# PowerSupply12v30A.net
KiCad netlist of a schematic drawn in Altium Designer
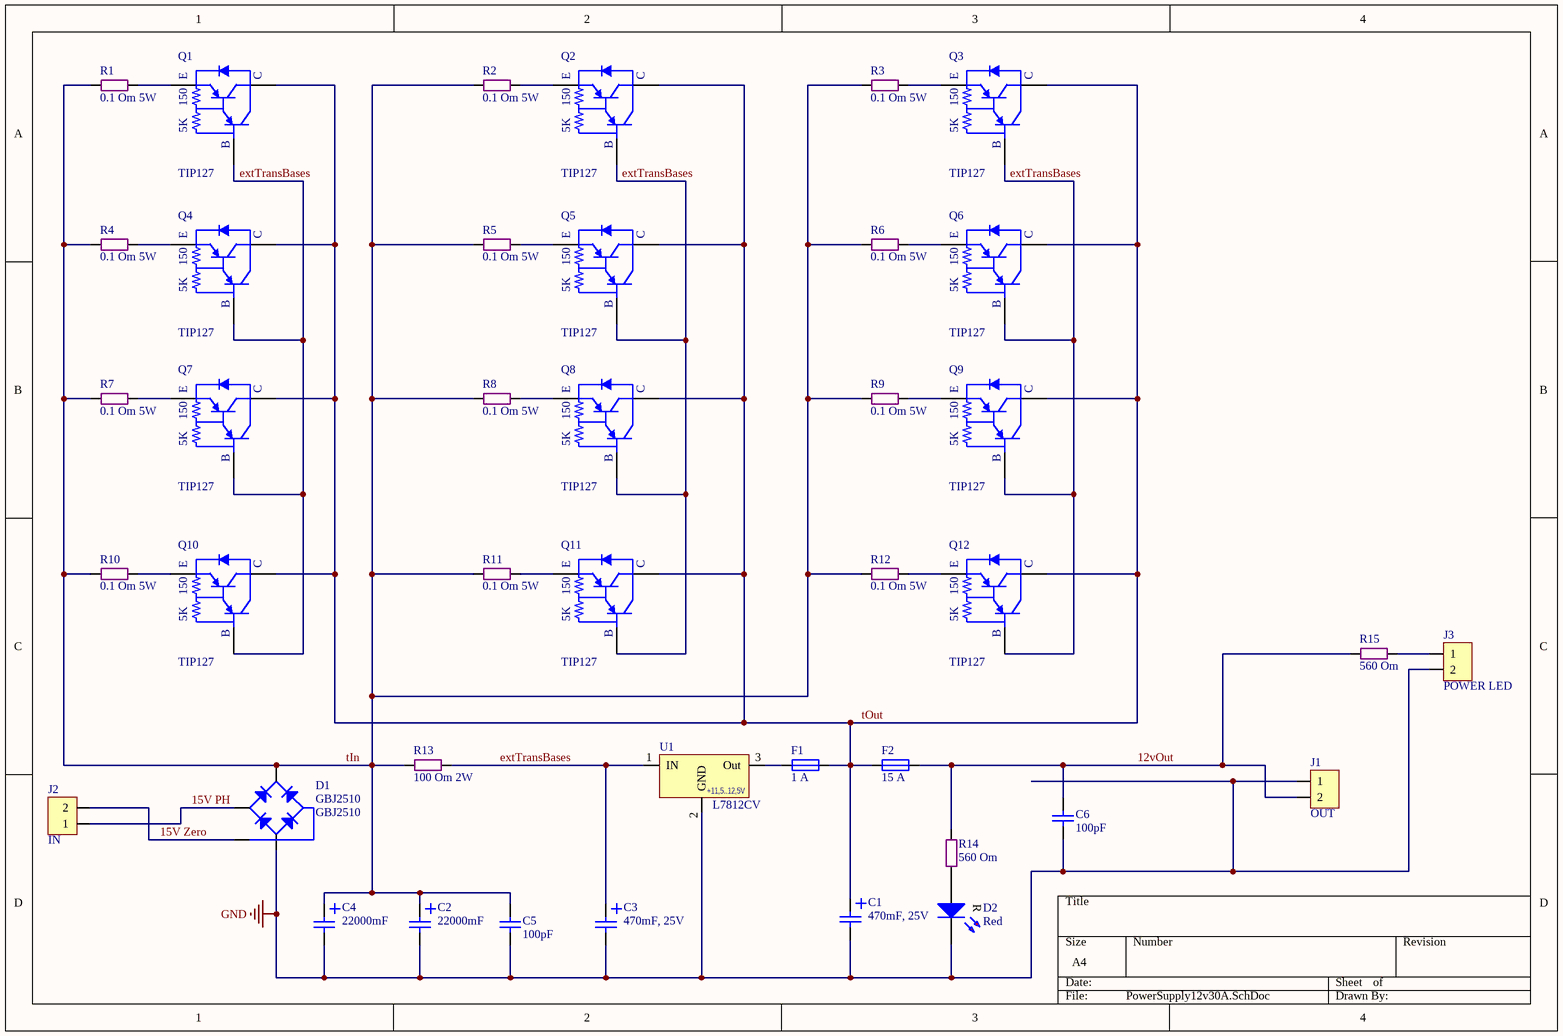
[diagram p0: PowerSupply12v30A.SchDoc]

(export (version "E")
  (design (tool "Eeschema 10.0.6"))
  (components
    (comp (ref "C1")
      (value "470mF, 25V")
      (footprint "Capacitor:Cap E p3.5mm D8xH12")
      (description "Capacitor")
      (libsource (lib "Capacitor") (part "Cap E 470mF x 25V"))
    )
    (comp (ref "C2")
      (value "22000mF")
      (footprint "Capacitor:Cap E p10mm D30mm (4p)")
      (description "Capacitor")
      (libsource (lib "Capacitor") (part "Cap E 22000mF x 25V"))
    )
    (comp (ref "C3")
      (value "470mF, 25V")
      (footprint "Capacitor:Cap E p3.5mm D8xH12")
      (description "Capacitor")
      (libsource (lib "Capacitor") (part "Cap E 470mF x 25V"))
    )
    (comp (ref "C4")
      (value "22000mF")
      (footprint "Capacitor:Cap E p10mm D30mm (4p)")
      (description "Capacitor")
      (libsource (lib "Capacitor") (part "Cap E 22000mF x 25V"))
    )
    (comp (ref "C5")
      (value "100pF")
      (footprint "Capacitor:SMD 1206 (3216)")
      (description "Capacitor")
      (libsource (lib "Capacitor") (part "Cap SMD 0402-1812"))
    )
    (comp (ref "C6")
      (value "100pF")
      (footprint "Capacitor:SMD 0805 (2012)")
      (description "Capacitor")
      (libsource (lib "Capacitor") (part "Cap SMD 0402-1812"))
    )
    (comp (ref "D1")
      (value "GBJ2510")
      (footprint "Diodes:GBJ")
      (description "25 A Diode Bridge")
      (fields (field (name "VOLTAGE") "1000V") (field (name "ALTIUM_VALUE") "GBJ2510"))
      (libsource (lib "Diodes") (part "Bridge GBJ2510"))
    )
    (comp (ref "D2")
      (value "Red")
      (footprint "LED:LED Round 5mm red")
      (description "1.8-2v 20mA, 4-5cd")
      (libsource (lib "LED") (part "Led Round 5mm Red"))
    )
    (comp (ref "F1")
      (value "1 A")
      (footprint "PassiveComponents:Fuse 9p")
      (description "Round fuse")
      (libsource (lib "PassiveComponents") (part "Fuse"))
    )
    (comp (ref "F2")
      (value "15 A")
      (footprint "PassiveComponents:Fuse 9p")
      (description "Round fuse")
      (libsource (lib "PassiveComponents") (part "Fuse"))
    )
    (comp (ref "J1")
      (value "OUT")
      (footprint "Connector:DG301 5mm 2p")
      (description "DG301 series")
      (libsource (lib "Connector") (part "DG301-5.0-2P12"))
    )
    (comp (ref "J2")
      (value "IN")
      (footprint "Connector:DG301 5mm 2p")
      (description "DG301 series")
      (libsource (lib "") (part "DG301-5.0-2P12_1"))
    )
    (comp (ref "J3")
      (value "POWER LED")
      (footprint "Connector:CWF-2 R")
      (description "CWF series")
      (libsource (lib "Connector") (part "CWF-2 (R)"))
    )
    (comp (ref "Q1")
      (value "TIP127")
      (footprint "GeneralCases:TO220-2")
      (description "PNP Darlington Bipolar Transistor")
      (libsource (lib "Transistor") (part "TIP127"))
    )
    (comp (ref "Q2")
      (value "TIP127")
      (footprint "GeneralCases:TO220-2")
      (description "PNP Darlington Bipolar Transistor")
      (libsource (lib "Transistor") (part "TIP127"))
    )
    (comp (ref "Q3")
      (value "TIP127")
      (footprint "GeneralCases:TO220-2")
      (description "PNP Darlington Bipolar Transistor")
      (libsource (lib "Transistor") (part "TIP127"))
    )
    (comp (ref "Q4")
      (value "TIP127")
      (footprint "GeneralCases:TO220-2")
      (description "PNP Darlington Bipolar Transistor")
      (libsource (lib "Transistor") (part "TIP127"))
    )
    (comp (ref "Q5")
      (value "TIP127")
      (footprint "GeneralCases:TO220-2")
      (description "PNP Darlington Bipolar Transistor")
      (libsource (lib "Transistor") (part "TIP127"))
    )
    (comp (ref "Q6")
      (value "TIP127")
      (footprint "GeneralCases:TO220-2")
      (description "PNP Darlington Bipolar Transistor")
      (libsource (lib "Transistor") (part "TIP127"))
    )
    (comp (ref "Q7")
      (value "TIP127")
      (footprint "GeneralCases:TO220-2")
      (description "PNP Darlington Bipolar Transistor")
      (libsource (lib "Transistor") (part "TIP127"))
    )
    (comp (ref "Q8")
      (value "TIP127")
      (footprint "GeneralCases:TO220-2")
      (description "PNP Darlington Bipolar Transistor")
      (libsource (lib "Transistor") (part "TIP127"))
    )
    (comp (ref "Q9")
      (value "TIP127")
      (footprint "GeneralCases:TO220-2")
      (description "PNP Darlington Bipolar Transistor")
      (libsource (lib "Transistor") (part "TIP127"))
    )
    (comp (ref "Q10")
      (value "TIP127")
      (footprint "GeneralCases:TO220-2")
      (description "PNP Darlington Bipolar Transistor")
      (libsource (lib "Transistor") (part "TIP127"))
    )
    (comp (ref "Q11")
      (value "TIP127")
      (footprint "GeneralCases:TO220-2")
      (description "PNP Darlington Bipolar Transistor")
      (libsource (lib "Transistor") (part "TIP127"))
    )
    (comp (ref "Q12")
      (value "TIP127")
      (footprint "GeneralCases:TO220-2")
      (description "PNP Darlington Bipolar Transistor")
      (libsource (lib "Transistor") (part "TIP127"))
    )
    (comp (ref "R1")
      (value "0.1 Om 5W")
      (footprint "PassiveComponents:Res 5W L22mm, p30mm")
      (description "5W Cement")
      (libsource (lib "PassiveComponents") (part "Res 5W"))
    )
    (comp (ref "R2")
      (value "0.1 Om 5W")
      (footprint "PassiveComponents:Res 5W L22mm, p30mm")
      (description "5W Cement")
      (libsource (lib "PassiveComponents") (part "Res 5W"))
    )
    (comp (ref "R3")
      (value "0.1 Om 5W")
      (footprint "PassiveComponents:Res 5W L22mm, p30mm")
      (description "5W Cement")
      (libsource (lib "PassiveComponents") (part "Res 5W"))
    )
    (comp (ref "R4")
      (value "0.1 Om 5W")
      (footprint "PassiveComponents:Res 5W L22mm, p30mm")
      (description "5W Cement")
      (libsource (lib "PassiveComponents") (part "Res 5W"))
    )
    (comp (ref "R5")
      (value "0.1 Om 5W")
      (footprint "PassiveComponents:Res 5W L22mm, p30mm")
      (description "5W Cement")
      (libsource (lib "PassiveComponents") (part "Res 5W"))
    )
    (comp (ref "R6")
      (value "0.1 Om 5W")
      (footprint "PassiveComponents:Res 5W L22mm, p30mm")
      (description "5W Cement")
      (libsource (lib "PassiveComponents") (part "Res 5W"))
    )
    (comp (ref "R7")
      (value "0.1 Om 5W")
      (footprint "PassiveComponents:Res 5W L22mm, p30mm")
      (description "5W Cement")
      (libsource (lib "PassiveComponents") (part "Res 5W"))
    )
    (comp (ref "R8")
      (value "0.1 Om 5W")
      (footprint "PassiveComponents:Res 5W L22mm, p30mm")
      (description "5W Cement")
      (libsource (lib "PassiveComponents") (part "Res 5W"))
    )
    (comp (ref "R9")
      (value "0.1 Om 5W")
      (footprint "PassiveComponents:Res 5W L22mm, p30mm")
      (description "5W Cement")
      (libsource (lib "PassiveComponents") (part "Res 5W"))
    )
    (comp (ref "R10")
      (value "0.1 Om 5W")
      (footprint "PassiveComponents:Res 5W L22mm, p30mm")
      (description "5W Cement")
      (libsource (lib "PassiveComponents") (part "Res 5W"))
    )
    (comp (ref "R11")
      (value "0.1 Om 5W")
      (footprint "PassiveComponents:Res 5W L22mm, p30mm")
      (description "5W Cement")
      (libsource (lib "PassiveComponents") (part "Res 5W"))
    )
    (comp (ref "R12")
      (value "0.1 Om 5W")
      (footprint "PassiveComponents:Res 5W L22mm, p30mm")
      (description "5W Cement")
      (libsource (lib "PassiveComponents") (part "Res 5W"))
    )
    (comp (ref "R13")
      (value "100 Om 2W")
      (footprint "PassiveComponents:Res p20.32 (9p) 2w")
      (description "5W Cement")
      (libsource (lib "PassiveComponents") (part "Res 2W"))
    )
    (comp (ref "R14")
      (value "560 Om")
      (footprint "PassiveComponents:Res p7.62 (4p) 0.25w")
      (libsource (lib "PassiveComponents") (part "Res Carbon"))
    )
    (comp (ref "R15")
      (value "560 Om")
      (footprint "PassiveComponents:Res p7.62 (4p) 0.25w")
      (libsource (lib "PassiveComponents") (part "Res Carbon"))
    )
    (comp (ref "U1")
      (value "L7812CV")
      (footprint "GeneralCases:TO220-2")
      (description "Voltage Regulator")
      (fields (field (name "MANUFACTURER") "ST") (field (name "V OUT") "+11,5..12,5V"))
      (libsource (lib "PowerAdjusment") (part "L7812CV"))
    )
  )
  (nets
    (net (code "1") (name "/12vOut") (class "Default")
      (node (ref "C6") (pin "1") (pinfunction "1_1") (pintype "passive"))
      (node (ref "F2") (pin "2") (pinfunction "2_2") (pintype "passive"))
      (node (ref "J1") (pin "2") (pinfunction "2_2") (pintype "passive"))
      (node (ref "R14") (pin "2") (pinfunction "2_2") (pintype "passive"))
      (node (ref "R15") (pin "2") (pinfunction "2_2") (pintype "passive"))
    )
    (net (code "2") (name "/15V PH") (class "Default")
      (node (ref "D1") (pin "P") (pinfunction "Ph_P") (pintype "passive"))
      (node (ref "J2") (pin "1") (pinfunction "1_1") (pintype "passive"))
    )
    (net (code "3") (name "/15V Zero") (class "Default")
      (node (ref "D1") (pin "Z") (pinfunction "Z_Z") (pintype "passive"))
      (node (ref "J2") (pin "2") (pinfunction "2_2") (pintype "passive"))
    )
    (net (code "4") (name "/extTransBases") (class "Default")
      (node (ref "C3") (pin "1") (pinfunction "1_1") (pintype "passive"))
      (node (ref "Q1") (pin "1") (pinfunction "B_1") (pintype "passive"))
      (node (ref "Q10") (pin "1") (pinfunction "B_1") (pintype "passive"))
      (node (ref "Q11") (pin "1") (pinfunction "B_1") (pintype "passive"))
      (node (ref "Q12") (pin "1") (pinfunction "B_1") (pintype "passive"))
      (node (ref "Q2") (pin "1") (pinfunction "B_1") (pintype "passive"))
      (node (ref "Q3") (pin "1") (pinfunction "B_1") (pintype "passive"))
      (node (ref "Q4") (pin "1") (pinfunction "B_1") (pintype "passive"))
      (node (ref "Q5") (pin "1") (pinfunction "B_1") (pintype "passive"))
      (node (ref "Q6") (pin "1") (pinfunction "B_1") (pintype "passive"))
      (node (ref "Q7") (pin "1") (pinfunction "B_1") (pintype "passive"))
      (node (ref "Q8") (pin "1") (pinfunction "B_1") (pintype "passive"))
      (node (ref "Q9") (pin "1") (pinfunction "B_1") (pintype "passive"))
      (node (ref "R13") (pin "2") (pinfunction "2_2") (pintype "passive"))
      (node (ref "U1") (pin "1") (pinfunction "IN_1") (pintype "power_in"))
    )
    (net (code "5") (name "/tIn") (class "Default")
      (node (ref "C2") (pin "1") (pinfunction "1_1") (pintype "passive"))
      (node (ref "C4") (pin "1") (pinfunction "1_1") (pintype "passive"))
      (node (ref "C5") (pin "1") (pinfunction "1_1") (pintype "passive"))
      (node (ref "D1") (pin "V") (pinfunction "V_V") (pintype "passive"))
      (node (ref "R1") (pin "1") (pinfunction "1_1") (pintype "passive"))
      (node (ref "R10") (pin "1") (pinfunction "1_1") (pintype "passive"))
      (node (ref "R11") (pin "1") (pinfunction "1_1") (pintype "passive"))
      (node (ref "R12") (pin "1") (pinfunction "1_1") (pintype "passive"))
      (node (ref "R13") (pin "1") (pinfunction "1_1") (pintype "passive"))
      (node (ref "R2") (pin "1") (pinfunction "1_1") (pintype "passive"))
      (node (ref "R3") (pin "1") (pinfunction "1_1") (pintype "passive"))
      (node (ref "R4") (pin "1") (pinfunction "1_1") (pintype "passive"))
      (node (ref "R5") (pin "1") (pinfunction "1_1") (pintype "passive"))
      (node (ref "R6") (pin "1") (pinfunction "1_1") (pintype "passive"))
      (node (ref "R7") (pin "1") (pinfunction "1_1") (pintype "passive"))
      (node (ref "R8") (pin "1") (pinfunction "1_1") (pintype "passive"))
      (node (ref "R9") (pin "1") (pinfunction "1_1") (pintype "passive"))
    )
    (net (code "6") (name "/tOut") (class "Default")
      (node (ref "C1") (pin "1") (pinfunction "1_1") (pintype "passive"))
      (node (ref "F1") (pin "2") (pinfunction "2_2") (pintype "passive"))
      (node (ref "F2") (pin "1") (pinfunction "1_1") (pintype "passive"))
      (node (ref "Q1") (pin "2") (pinfunction "C_2") (pintype "passive"))
      (node (ref "Q10") (pin "2") (pinfunction "C_2") (pintype "passive"))
      (node (ref "Q11") (pin "2") (pinfunction "C_2") (pintype "passive"))
      (node (ref "Q12") (pin "2") (pinfunction "C_2") (pintype "passive"))
      (node (ref "Q2") (pin "2") (pinfunction "C_2") (pintype "passive"))
      (node (ref "Q3") (pin "2") (pinfunction "C_2") (pintype "passive"))
      (node (ref "Q4") (pin "2") (pinfunction "C_2") (pintype "passive"))
      (node (ref "Q5") (pin "2") (pinfunction "C_2") (pintype "passive"))
      (node (ref "Q6") (pin "2") (pinfunction "C_2") (pintype "passive"))
      (node (ref "Q7") (pin "2") (pinfunction "C_2") (pintype "passive"))
      (node (ref "Q8") (pin "2") (pinfunction "C_2") (pintype "passive"))
      (node (ref "Q9") (pin "2") (pinfunction "C_2") (pintype "passive"))
    )
    (net (code "7") (name "GND") (class "Default")
      (node (ref "C1") (pin "2") (pinfunction "2_2") (pintype "passive"))
      (node (ref "C2") (pin "2") (pinfunction "2_2") (pintype "passive"))
      (node (ref "C3") (pin "2") (pinfunction "2_2") (pintype "passive"))
      (node (ref "C4") (pin "2") (pinfunction "2_2") (pintype "passive"))
      (node (ref "C5") (pin "2") (pinfunction "2_2") (pintype "passive"))
      (node (ref "C6") (pin "2") (pinfunction "2_2") (pintype "passive"))
      (node (ref "D1") (pin "G") (pinfunction "G_G") (pintype "passive"))
      (node (ref "D2") (pin "K") (pinfunction "K_K") (pintype "passive"))
      (node (ref "J1") (pin "1") (pinfunction "1_1") (pintype "passive"))
      (node (ref "J3") (pin "2") (pinfunction "2_2") (pintype "passive"))
      (node (ref "U1") (pin "2") (pinfunction "GND_2") (pintype "passive"))
    )
    (net (code "8") (name "Net-(D2-PadA)") (class "Default")
      (node (ref "D2") (pin "A") (pinfunction "A_A") (pintype "passive"))
      (node (ref "R14") (pin "1") (pinfunction "1_1") (pintype "passive"))
    )
    (net (code "9") (name "Net-(J3-Pad1)") (class "Default")
      (node (ref "J3") (pin "1") (pinfunction "1_1") (pintype "passive"))
      (node (ref "R15") (pin "1") (pinfunction "1_1") (pintype "passive"))
    )
    (net (code "10") (name "Net-(Q1-E)") (class "Default")
      (node (ref "Q1") (pin "3") (pinfunction "E_3") (pintype "passive"))
      (node (ref "R1") (pin "2") (pinfunction "2_2") (pintype "passive"))
    )
    (net (code "11") (name "Net-(Q2-E)") (class "Default")
      (node (ref "Q2") (pin "3") (pinfunction "E_3") (pintype "passive"))
      (node (ref "R2") (pin "2") (pinfunction "2_2") (pintype "passive"))
    )
    (net (code "12") (name "Net-(Q3-E)") (class "Default")
      (node (ref "Q3") (pin "3") (pinfunction "E_3") (pintype "passive"))
      (node (ref "R3") (pin "2") (pinfunction "2_2") (pintype "passive"))
    )
    (net (code "13") (name "Net-(Q4-E)") (class "Default")
      (node (ref "Q4") (pin "3") (pinfunction "E_3") (pintype "passive"))
      (node (ref "R4") (pin "2") (pinfunction "2_2") (pintype "passive"))
    )
    (net (code "14") (name "Net-(Q5-E)") (class "Default")
      (node (ref "Q5") (pin "3") (pinfunction "E_3") (pintype "passive"))
      (node (ref "R5") (pin "2") (pinfunction "2_2") (pintype "passive"))
    )
    (net (code "15") (name "Net-(Q6-E)") (class "Default")
      (node (ref "Q6") (pin "3") (pinfunction "E_3") (pintype "passive"))
      (node (ref "R6") (pin "2") (pinfunction "2_2") (pintype "passive"))
    )
    (net (code "16") (name "Net-(Q7-E)") (class "Default")
      (node (ref "Q7") (pin "3") (pinfunction "E_3") (pintype "passive"))
      (node (ref "R7") (pin "2") (pinfunction "2_2") (pintype "passive"))
    )
    (net (code "17") (name "Net-(Q8-E)") (class "Default")
      (node (ref "Q8") (pin "3") (pinfunction "E_3") (pintype "passive"))
      (node (ref "R8") (pin "2") (pinfunction "2_2") (pintype "passive"))
    )
    (net (code "18") (name "Net-(Q9-E)") (class "Default")
      (node (ref "Q9") (pin "3") (pinfunction "E_3") (pintype "passive"))
      (node (ref "R9") (pin "2") (pinfunction "2_2") (pintype "passive"))
    )
    (net (code "19") (name "Net-(Q10-E)") (class "Default")
      (node (ref "Q10") (pin "3") (pinfunction "E_3") (pintype "passive"))
      (node (ref "R10") (pin "2") (pinfunction "2_2") (pintype "passive"))
    )
    (net (code "20") (name "Net-(Q11-E)") (class "Default")
      (node (ref "Q11") (pin "3") (pinfunction "E_3") (pintype "passive"))
      (node (ref "R11") (pin "2") (pinfunction "2_2") (pintype "passive"))
    )
    (net (code "21") (name "Net-(Q12-E)") (class "Default")
      (node (ref "Q12") (pin "3") (pinfunction "E_3") (pintype "passive"))
      (node (ref "R12") (pin "2") (pinfunction "2_2") (pintype "passive"))
    )
    (net (code "22") (name "Net-(U1-Out)") (class "Default")
      (node (ref "F1") (pin "1") (pinfunction "1_1") (pintype "passive"))
      (node (ref "U1") (pin "3") (pinfunction "Out_3") (pintype "power_in"))
    )
  )
)
